# diagrama_robot.net
KiCad netlist of a schematic drawn in EAGLE
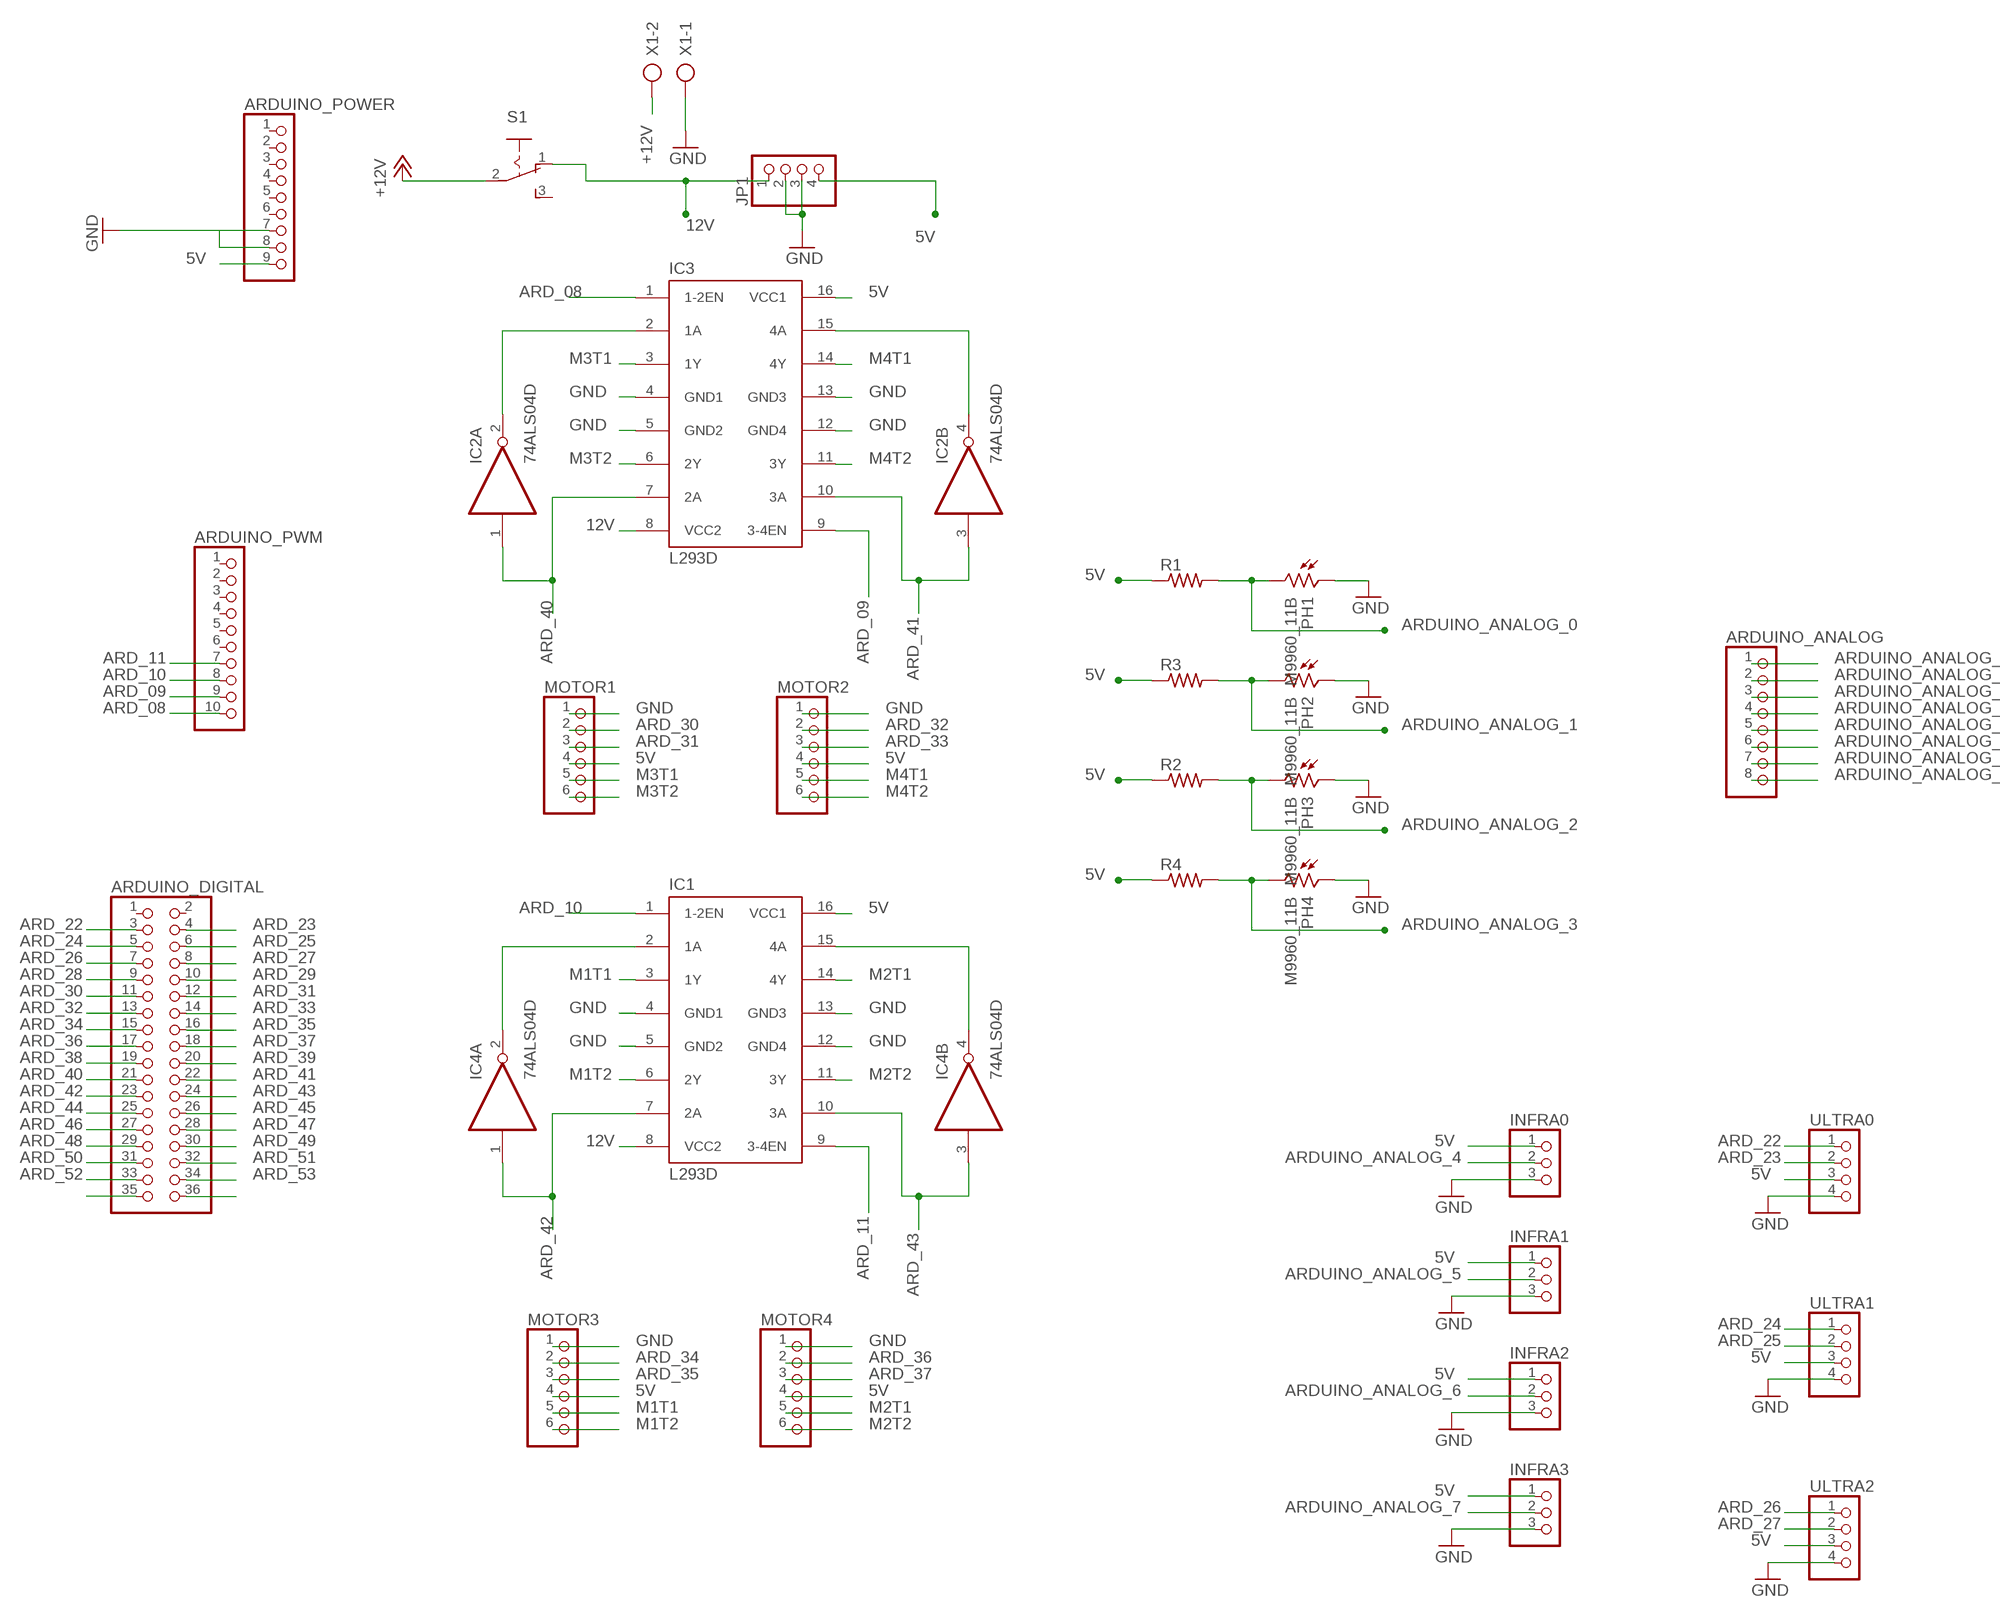
[diagram p0: schematic, sheet 1]

(export (version "E")
  (design (tool "Eeschema 10.0.6"))
  (components
    (comp (ref "ARDUINO_ANALOG")
      (value "PINHD-1X8")
      (footprint "eagle-import:1X08")
      (libsource (lib "eagle-import") (part "PINHD-1X8"))
    )
    (comp (ref "ARDUINO_DIGITAL")
      (value "PINHD-2X18")
      (footprint "eagle-import:2X18")
      (libsource (lib "eagle-import") (part "PINHD-2X18"))
    )
    (comp (ref "ARDUINO_POWER")
      (value "PINHD-1X9")
      (footprint "eagle-import:1X09")
      (libsource (lib "eagle-import") (part "PINHD-1X9"))
    )
    (comp (ref "ARDUINO_PWM")
      (value "PINHD-1X10")
      (footprint "eagle-import:1X10")
      (libsource (lib "eagle-import") (part "PINHD-1X10"))
    )
    (comp (ref "IC1")
      (value "L293D")
      (footprint "eagle-import:DIL16")
      (libsource (lib "eagle-import") (part "L293D"))
    )
    (comp (ref "IC2")
      (value "74ALS04D")
      (footprint "eagle-import:SO14")
      (libsource (lib "eagle-import") (part "7404DALS"))
    )
    (comp (ref "IC3")
      (value "L293D")
      (footprint "eagle-import:DIL16")
      (libsource (lib "eagle-import") (part "L293D"))
    )
    (comp (ref "IC4")
      (value "74ALS04D")
      (footprint "eagle-import:SO14")
      (libsource (lib "eagle-import") (part "7404DALS"))
    )
    (comp (ref "INFRA0")
      (value "PINHD-1X3")
      (footprint "eagle-import:1X03")
      (libsource (lib "eagle-import") (part "PINHD-1X3"))
    )
    (comp (ref "INFRA1")
      (value "PINHD-1X3")
      (footprint "eagle-import:1X03")
      (libsource (lib "eagle-import") (part "PINHD-1X3"))
    )
    (comp (ref "INFRA2")
      (value "PINHD-1X3")
      (footprint "eagle-import:1X03")
      (libsource (lib "eagle-import") (part "PINHD-1X3"))
    )
    (comp (ref "INFRA3")
      (value "PINHD-1X3")
      (footprint "eagle-import:1X03")
      (libsource (lib "eagle-import") (part "PINHD-1X3"))
    )
    (comp (ref "JP1")
      (value "PINHD-1X4")
      (footprint "eagle-import:1X04")
      (libsource (lib "eagle-import") (part "PINHD-1X4"))
    )
    (comp (ref "MOTOR1")
      (value "PINHD-1X6")
      (footprint "eagle-import:1X06")
      (libsource (lib "eagle-import") (part "PINHD-1X6"))
    )
    (comp (ref "MOTOR2")
      (value "PINHD-1X6")
      (footprint "eagle-import:1X06")
      (libsource (lib "eagle-import") (part "PINHD-1X6"))
    )
    (comp (ref "MOTOR3")
      (value "PINHD-1X6")
      (footprint "eagle-import:1X06")
      (libsource (lib "eagle-import") (part "PINHD-1X6"))
    )
    (comp (ref "MOTOR4")
      (value "PINHD-1X6")
      (footprint "eagle-import:1X06")
      (libsource (lib "eagle-import") (part "PINHD-1X6"))
    )
    (comp (ref "PH1")
      (value "M9960_11B")
      (footprint "eagle-import:M9960")
      (libsource (lib "eagle-import") (part "M9960_11B"))
    )
    (comp (ref "PH2")
      (value "M9960_11B")
      (footprint "eagle-import:M9960")
      (libsource (lib "eagle-import") (part "M9960_11B"))
    )
    (comp (ref "PH3")
      (value "M9960_11B")
      (footprint "eagle-import:M9960")
      (libsource (lib "eagle-import") (part "M9960_11B"))
    )
    (comp (ref "PH4")
      (value "M9960_11B")
      (footprint "eagle-import:M9960")
      (libsource (lib "eagle-import") (part "M9960_11B"))
    )
    (comp (ref "R1")
      (value "R-US_0204/2V")
      (footprint "eagle-import:0204V")
      (libsource (lib "eagle-import") (part "R-US_0204/2V"))
    )
    (comp (ref "R2")
      (value "R-US_0204/2V")
      (footprint "eagle-import:0204V")
      (libsource (lib "eagle-import") (part "R-US_0204/2V"))
    )
    (comp (ref "R3")
      (value "R-US_0204/2V")
      (footprint "eagle-import:0204V")
      (libsource (lib "eagle-import") (part "R-US_0204/2V"))
    )
    (comp (ref "R4")
      (value "R-US_0204/2V")
      (footprint "eagle-import:0204V")
      (libsource (lib "eagle-import") (part "R-US_0204/2V"))
    )
    (comp (ref "S1")
      (value "255SB")
      (footprint "eagle-import:255SB")
      (libsource (lib "eagle-import") (part "255SB"))
    )
    (comp (ref "ULTRA0")
      (value "PINHD-1X4")
      (footprint "eagle-import:1X04")
      (libsource (lib "eagle-import") (part "PINHD-1X4"))
    )
    (comp (ref "ULTRA1")
      (value "PINHD-1X4")
      (footprint "eagle-import:1X04")
      (libsource (lib "eagle-import") (part "PINHD-1X4"))
    )
    (comp (ref "ULTRA2")
      (value "PINHD-1X4")
      (footprint "eagle-import:1X04")
      (libsource (lib "eagle-import") (part "PINHD-1X4"))
    )
    (comp (ref "X1")
      (value "AK500/2-H")
      (footprint "eagle-import:AK500_2-H")
      (libsource (lib "eagle-import") (part "AK500/2-H"))
    )
  )
  (nets
    (net (code "1") (name "+12V") (class "Default")
      (node (ref "S1") (pin "2") (pinfunction "P_2") (pintype "passive"))
      (node (ref "X1") (pin "2") (pinfunction "KL_2") (pintype "passive"))
    )
    (net (code "2") (name "/5V") (class "Default")
      (node (ref "ARDUINO_POWER") (pin "9") (pinfunction "9_9") (pintype "passive"))
      (node (ref "IC1") (pin "16") (pinfunction "VCC1_16") (pintype "power_in"))
      (node (ref "IC3") (pin "16") (pinfunction "VCC1_16") (pintype "power_in"))
      (node (ref "INFRA0") (pin "1") (pinfunction "1_1") (pintype "passive"))
      (node (ref "INFRA1") (pin "1") (pinfunction "1_1") (pintype "passive"))
      (node (ref "INFRA2") (pin "1") (pinfunction "1_1") (pintype "passive"))
      (node (ref "INFRA3") (pin "1") (pinfunction "1_1") (pintype "passive"))
      (node (ref "JP1") (pin "4") (pinfunction "4_4") (pintype "passive"))
      (node (ref "MOTOR1") (pin "4") (pinfunction "4_4") (pintype "passive"))
      (node (ref "MOTOR2") (pin "4") (pinfunction "4_4") (pintype "passive"))
      (node (ref "MOTOR3") (pin "4") (pinfunction "4_4") (pintype "passive"))
      (node (ref "MOTOR4") (pin "4") (pinfunction "4_4") (pintype "passive"))
      (node (ref "R1") (pin "1") (pinfunction "1_1") (pintype "passive"))
      (node (ref "R2") (pin "1") (pinfunction "1_1") (pintype "passive"))
      (node (ref "R3") (pin "1") (pinfunction "1_1") (pintype "passive"))
      (node (ref "R4") (pin "1") (pinfunction "1_1") (pintype "passive"))
      (node (ref "ULTRA0") (pin "3") (pinfunction "3_3") (pintype "passive"))
      (node (ref "ULTRA1") (pin "3") (pinfunction "3_3") (pintype "passive"))
      (node (ref "ULTRA2") (pin "3") (pinfunction "3_3") (pintype "passive"))
    )
    (net (code "3") (name "/12V") (class "Default")
      (node (ref "IC1") (pin "8") (pinfunction "VCC2_8") (pintype "power_in"))
      (node (ref "IC3") (pin "8") (pinfunction "VCC2_8") (pintype "power_in"))
      (node (ref "JP1") (pin "1") (pinfunction "1_1") (pintype "passive"))
      (node (ref "S1") (pin "1") (pinfunction "O_1") (pintype "passive"))
    )
    (net (code "4") (name "/ARDUINO_ANALOG_0") (class "Default")
      (node (ref "ARDUINO_ANALOG") (pin "1") (pinfunction "1_1") (pintype "passive"))
      (node (ref "PH1") (pin "2") (pinfunction "2_2") (pintype "passive"))
      (node (ref "R1") (pin "2") (pinfunction "2_2") (pintype "passive"))
    )
    (net (code "5") (name "/ARDUINO_ANALOG_1") (class "Default")
      (node (ref "ARDUINO_ANALOG") (pin "2") (pinfunction "2_2") (pintype "passive"))
      (node (ref "PH2") (pin "2") (pinfunction "2_2") (pintype "passive"))
      (node (ref "R3") (pin "2") (pinfunction "2_2") (pintype "passive"))
    )
    (net (code "6") (name "/ARDUINO_ANALOG_2") (class "Default")
      (node (ref "ARDUINO_ANALOG") (pin "3") (pinfunction "3_3") (pintype "passive"))
      (node (ref "PH3") (pin "2") (pinfunction "2_2") (pintype "passive"))
      (node (ref "R2") (pin "2") (pinfunction "2_2") (pintype "passive"))
    )
    (net (code "7") (name "/ARDUINO_ANALOG_3") (class "Default")
      (node (ref "ARDUINO_ANALOG") (pin "4") (pinfunction "4_4") (pintype "passive"))
      (node (ref "PH4") (pin "2") (pinfunction "2_2") (pintype "passive"))
      (node (ref "R4") (pin "2") (pinfunction "2_2") (pintype "passive"))
    )
    (net (code "8") (name "/ARDUINO_ANALOG_4") (class "Default")
      (node (ref "ARDUINO_ANALOG") (pin "5") (pinfunction "5_5") (pintype "passive"))
      (node (ref "INFRA0") (pin "2") (pinfunction "2_2") (pintype "passive"))
    )
    (net (code "9") (name "/ARDUINO_ANALOG_5") (class "Default")
      (node (ref "ARDUINO_ANALOG") (pin "6") (pinfunction "6_6") (pintype "passive"))
      (node (ref "INFRA1") (pin "2") (pinfunction "2_2") (pintype "passive"))
    )
    (net (code "10") (name "/ARDUINO_ANALOG_6") (class "Default")
      (node (ref "ARDUINO_ANALOG") (pin "7") (pinfunction "7_7") (pintype "passive"))
      (node (ref "INFRA2") (pin "2") (pinfunction "2_2") (pintype "passive"))
    )
    (net (code "11") (name "/ARDUINO_ANALOG_7") (class "Default")
      (node (ref "ARDUINO_ANALOG") (pin "8") (pinfunction "8_8") (pintype "passive"))
      (node (ref "INFRA3") (pin "2") (pinfunction "2_2") (pintype "passive"))
    )
    (net (code "12") (name "/ARD_08") (class "Default")
      (node (ref "ARDUINO_PWM") (pin "10") (pinfunction "10_10") (pintype "passive"))
      (node (ref "IC3") (pin "1") (pinfunction "1-2EN_1") (pintype "input"))
    )
    (net (code "13") (name "/ARD_09") (class "Default")
      (node (ref "ARDUINO_PWM") (pin "9") (pinfunction "9_9") (pintype "passive"))
      (node (ref "IC3") (pin "9") (pinfunction "3-4EN_9") (pintype "input"))
    )
    (net (code "14") (name "/ARD_10") (class "Default")
      (node (ref "ARDUINO_PWM") (pin "8") (pinfunction "8_8") (pintype "passive"))
      (node (ref "IC1") (pin "1") (pinfunction "1-2EN_1") (pintype "input"))
    )
    (net (code "15") (name "/ARD_11") (class "Default")
      (node (ref "ARDUINO_PWM") (pin "7") (pinfunction "7_7") (pintype "passive"))
      (node (ref "IC1") (pin "9") (pinfunction "3-4EN_9") (pintype "input"))
    )
    (net (code "16") (name "/ARD_22") (class "Default")
      (node (ref "ARDUINO_DIGITAL") (pin "3") (pinfunction "3_3") (pintype "passive"))
      (node (ref "ULTRA0") (pin "1") (pinfunction "1_1") (pintype "passive"))
    )
    (net (code "17") (name "/ARD_23") (class "Default")
      (node (ref "ARDUINO_DIGITAL") (pin "4") (pinfunction "4_4") (pintype "passive"))
      (node (ref "ULTRA0") (pin "2") (pinfunction "2_2") (pintype "passive"))
    )
    (net (code "18") (name "/ARD_24") (class "Default")
      (node (ref "ARDUINO_DIGITAL") (pin "5") (pinfunction "5_5") (pintype "passive"))
      (node (ref "ULTRA1") (pin "1") (pinfunction "1_1") (pintype "passive"))
    )
    (net (code "19") (name "/ARD_25") (class "Default")
      (node (ref "ARDUINO_DIGITAL") (pin "6") (pinfunction "6_6") (pintype "passive"))
      (node (ref "ULTRA1") (pin "2") (pinfunction "2_2") (pintype "passive"))
    )
    (net (code "20") (name "/ARD_26") (class "Default")
      (node (ref "ARDUINO_DIGITAL") (pin "7") (pinfunction "7_7") (pintype "passive"))
      (node (ref "ULTRA2") (pin "1") (pinfunction "1_1") (pintype "passive"))
    )
    (net (code "21") (name "/ARD_27") (class "Default")
      (node (ref "ARDUINO_DIGITAL") (pin "8") (pinfunction "8_8") (pintype "passive"))
      (node (ref "ULTRA2") (pin "2") (pinfunction "2_2") (pintype "passive"))
    )
    (net (code "22") (name "/ARD_28") (class "Default")
      (node (ref "ARDUINO_DIGITAL") (pin "9") (pinfunction "9_9") (pintype "passive"))
    )
    (net (code "23") (name "/ARD_29") (class "Default")
      (node (ref "ARDUINO_DIGITAL") (pin "10") (pinfunction "10_10") (pintype "passive"))
    )
    (net (code "24") (name "/ARD_30") (class "Default")
      (node (ref "ARDUINO_DIGITAL") (pin "11") (pinfunction "11_11") (pintype "passive"))
      (node (ref "MOTOR1") (pin "2") (pinfunction "2_2") (pintype "passive"))
    )
    (net (code "25") (name "/ARD_31") (class "Default")
      (node (ref "ARDUINO_DIGITAL") (pin "12") (pinfunction "12_12") (pintype "passive"))
      (node (ref "MOTOR1") (pin "3") (pinfunction "3_3") (pintype "passive"))
    )
    (net (code "26") (name "/ARD_32") (class "Default")
      (node (ref "ARDUINO_DIGITAL") (pin "13") (pinfunction "13_13") (pintype "passive"))
      (node (ref "MOTOR2") (pin "2") (pinfunction "2_2") (pintype "passive"))
    )
    (net (code "27") (name "/ARD_33") (class "Default")
      (node (ref "ARDUINO_DIGITAL") (pin "14") (pinfunction "14_14") (pintype "passive"))
      (node (ref "MOTOR2") (pin "3") (pinfunction "3_3") (pintype "passive"))
    )
    (net (code "28") (name "/ARD_34") (class "Default")
      (node (ref "ARDUINO_DIGITAL") (pin "15") (pinfunction "15_15") (pintype "passive"))
      (node (ref "MOTOR3") (pin "2") (pinfunction "2_2") (pintype "passive"))
    )
    (net (code "29") (name "/ARD_35") (class "Default")
      (node (ref "ARDUINO_DIGITAL") (pin "16") (pinfunction "16_16") (pintype "passive"))
      (node (ref "MOTOR3") (pin "3") (pinfunction "3_3") (pintype "passive"))
    )
    (net (code "30") (name "/ARD_36") (class "Default")
      (node (ref "ARDUINO_DIGITAL") (pin "17") (pinfunction "17_17") (pintype "passive"))
      (node (ref "MOTOR4") (pin "2") (pinfunction "2_2") (pintype "passive"))
    )
    (net (code "31") (name "/ARD_37") (class "Default")
      (node (ref "ARDUINO_DIGITAL") (pin "18") (pinfunction "18_18") (pintype "passive"))
      (node (ref "MOTOR4") (pin "3") (pinfunction "3_3") (pintype "passive"))
    )
    (net (code "32") (name "/ARD_38") (class "Default")
      (node (ref "ARDUINO_DIGITAL") (pin "19") (pinfunction "19_19") (pintype "passive"))
    )
    (net (code "33") (name "/ARD_39") (class "Default")
      (node (ref "ARDUINO_DIGITAL") (pin "20") (pinfunction "20_20") (pintype "passive"))
    )
    (net (code "34") (name "/ARD_40") (class "Default")
      (node (ref "ARDUINO_DIGITAL") (pin "21") (pinfunction "21_21") (pintype "passive"))
      (node (ref "IC2") (pin "1") (pinfunction "I_1") (pintype "input"))
      (node (ref "IC3") (pin "7") (pinfunction "2A_7") (pintype "input"))
    )
    (net (code "35") (name "/ARD_41") (class "Default")
      (node (ref "ARDUINO_DIGITAL") (pin "22") (pinfunction "22_22") (pintype "passive"))
      (node (ref "IC2") (pin "3") (pinfunction "I_3") (pintype "input"))
      (node (ref "IC3") (pin "10") (pinfunction "3A_10") (pintype "input"))
    )
    (net (code "36") (name "/ARD_42") (class "Default")
      (node (ref "ARDUINO_DIGITAL") (pin "23") (pinfunction "23_23") (pintype "passive"))
      (node (ref "IC1") (pin "7") (pinfunction "2A_7") (pintype "input"))
      (node (ref "IC4") (pin "1") (pinfunction "I_1") (pintype "input"))
    )
    (net (code "37") (name "/ARD_43") (class "Default")
      (node (ref "ARDUINO_DIGITAL") (pin "24") (pinfunction "24_24") (pintype "passive"))
      (node (ref "IC1") (pin "10") (pinfunction "3A_10") (pintype "input"))
      (node (ref "IC4") (pin "3") (pinfunction "I_3") (pintype "input"))
    )
    (net (code "38") (name "/ARD_44") (class "Default")
      (node (ref "ARDUINO_DIGITAL") (pin "25") (pinfunction "25_25") (pintype "passive"))
    )
    (net (code "39") (name "/ARD_45") (class "Default")
      (node (ref "ARDUINO_DIGITAL") (pin "26") (pinfunction "26_26") (pintype "passive"))
    )
    (net (code "40") (name "/ARD_46") (class "Default")
      (node (ref "ARDUINO_DIGITAL") (pin "27") (pinfunction "27_27") (pintype "passive"))
    )
    (net (code "41") (name "/ARD_47") (class "Default")
      (node (ref "ARDUINO_DIGITAL") (pin "28") (pinfunction "28_28") (pintype "passive"))
    )
    (net (code "42") (name "/ARD_48") (class "Default")
      (node (ref "ARDUINO_DIGITAL") (pin "29") (pinfunction "29_29") (pintype "passive"))
    )
    (net (code "43") (name "/ARD_49") (class "Default")
      (node (ref "ARDUINO_DIGITAL") (pin "30") (pinfunction "30_30") (pintype "passive"))
    )
    (net (code "44") (name "/ARD_50") (class "Default")
      (node (ref "ARDUINO_DIGITAL") (pin "31") (pinfunction "31_31") (pintype "passive"))
    )
    (net (code "45") (name "/ARD_51") (class "Default")
      (node (ref "ARDUINO_DIGITAL") (pin "32") (pinfunction "32_32") (pintype "passive"))
    )
    (net (code "46") (name "/ARD_52") (class "Default")
      (node (ref "ARDUINO_DIGITAL") (pin "33") (pinfunction "33_33") (pintype "passive"))
    )
    (net (code "47") (name "/ARD_53") (class "Default")
      (node (ref "ARDUINO_DIGITAL") (pin "34") (pinfunction "34_34") (pintype "passive"))
    )
    (net (code "48") (name "/M1T1") (class "Default")
      (node (ref "IC1") (pin "3") (pinfunction "1Y_3") (pintype "output"))
      (node (ref "MOTOR3") (pin "5") (pinfunction "5_5") (pintype "passive"))
    )
    (net (code "49") (name "/M1T2") (class "Default")
      (node (ref "IC1") (pin "6") (pinfunction "2Y_6") (pintype "output"))
      (node (ref "MOTOR3") (pin "6") (pinfunction "6_6") (pintype "passive"))
    )
    (net (code "50") (name "/M2T1") (class "Default")
      (node (ref "IC1") (pin "14") (pinfunction "4Y_14") (pintype "output"))
      (node (ref "MOTOR4") (pin "5") (pinfunction "5_5") (pintype "passive"))
    )
    (net (code "51") (name "/M2T2") (class "Default")
      (node (ref "IC1") (pin "11") (pinfunction "3Y_11") (pintype "output"))
      (node (ref "MOTOR4") (pin "6") (pinfunction "6_6") (pintype "passive"))
    )
    (net (code "52") (name "/M3T1") (class "Default")
      (node (ref "IC3") (pin "3") (pinfunction "1Y_3") (pintype "output"))
      (node (ref "MOTOR1") (pin "5") (pinfunction "5_5") (pintype "passive"))
    )
    (net (code "53") (name "/M3T2") (class "Default")
      (node (ref "IC3") (pin "6") (pinfunction "2Y_6") (pintype "output"))
      (node (ref "MOTOR1") (pin "6") (pinfunction "6_6") (pintype "passive"))
    )
    (net (code "54") (name "/M4T1") (class "Default")
      (node (ref "IC3") (pin "14") (pinfunction "4Y_14") (pintype "output"))
      (node (ref "MOTOR2") (pin "5") (pinfunction "5_5") (pintype "passive"))
    )
    (net (code "55") (name "/M4T2") (class "Default")
      (node (ref "IC3") (pin "11") (pinfunction "3Y_11") (pintype "output"))
      (node (ref "MOTOR2") (pin "6") (pinfunction "6_6") (pintype "passive"))
    )
    (net (code "56") (name "GND") (class "Default")
      (node (ref "ARDUINO_POWER") (pin "7") (pinfunction "7_7") (pintype "passive"))
      (node (ref "ARDUINO_POWER") (pin "8") (pinfunction "8_8") (pintype "passive"))
      (node (ref "IC1") (pin "12") (pinfunction "GND4_12") (pintype "power_in"))
      (node (ref "IC1") (pin "13") (pinfunction "GND3_13") (pintype "power_in"))
      (node (ref "IC1") (pin "4") (pinfunction "GND1_4") (pintype "power_in"))
      (node (ref "IC1") (pin "5") (pinfunction "GND2_5") (pintype "power_in"))
      (node (ref "IC3") (pin "12") (pinfunction "GND4_12") (pintype "power_in"))
      (node (ref "IC3") (pin "13") (pinfunction "GND3_13") (pintype "power_in"))
      (node (ref "IC3") (pin "4") (pinfunction "GND1_4") (pintype "power_in"))
      (node (ref "IC3") (pin "5") (pinfunction "GND2_5") (pintype "power_in"))
      (node (ref "INFRA0") (pin "3") (pinfunction "3_3") (pintype "passive"))
      (node (ref "INFRA1") (pin "3") (pinfunction "3_3") (pintype "passive"))
      (node (ref "INFRA2") (pin "3") (pinfunction "3_3") (pintype "passive"))
      (node (ref "INFRA3") (pin "3") (pinfunction "3_3") (pintype "passive"))
      (node (ref "JP1") (pin "2") (pinfunction "2_2") (pintype "passive"))
      (node (ref "JP1") (pin "3") (pinfunction "3_3") (pintype "passive"))
      (node (ref "MOTOR1") (pin "1") (pinfunction "1_1") (pintype "passive"))
      (node (ref "MOTOR2") (pin "1") (pinfunction "1_1") (pintype "passive"))
      (node (ref "MOTOR3") (pin "1") (pinfunction "1_1") (pintype "passive"))
      (node (ref "MOTOR4") (pin "1") (pinfunction "1_1") (pintype "passive"))
      (node (ref "PH1") (pin "1") (pinfunction "1_1") (pintype "passive"))
      (node (ref "PH2") (pin "1") (pinfunction "1_1") (pintype "passive"))
      (node (ref "PH3") (pin "1") (pinfunction "1_1") (pintype "passive"))
      (node (ref "PH4") (pin "1") (pinfunction "1_1") (pintype "passive"))
      (node (ref "ULTRA0") (pin "4") (pinfunction "4_4") (pintype "passive"))
      (node (ref "ULTRA1") (pin "4") (pinfunction "4_4") (pintype "passive"))
      (node (ref "ULTRA2") (pin "4") (pinfunction "4_4") (pintype "passive"))
      (node (ref "X1") (pin "1") (pinfunction "KL_1") (pintype "passive"))
    )
    (net (code "57") (name "Net-(IC1-1A)") (class "Default")
      (node (ref "IC1") (pin "2") (pinfunction "1A_2") (pintype "input"))
      (node (ref "IC4") (pin "2") (pinfunction "O_2") (pintype "output"))
    )
    (net (code "58") (name "Net-(IC1-4A)") (class "Default")
      (node (ref "IC1") (pin "15") (pinfunction "4A_15") (pintype "input"))
      (node (ref "IC4") (pin "4") (pinfunction "O_4") (pintype "output"))
    )
    (net (code "59") (name "Net-(IC2A-O)") (class "Default")
      (node (ref "IC2") (pin "2") (pinfunction "O_2") (pintype "output"))
      (node (ref "IC3") (pin "2") (pinfunction "1A_2") (pintype "input"))
    )
    (net (code "60") (name "Net-(IC2B-O)") (class "Default")
      (node (ref "IC2") (pin "4") (pinfunction "O_4") (pintype "output"))
      (node (ref "IC3") (pin "15") (pinfunction "4A_15") (pintype "input"))
    )
    (net (code "61") (name "unconnected-(ARDUINO_DIGITAL-Pad1)") (class "Default")
      (node (ref "ARDUINO_DIGITAL") (pin "1") (pinfunction "1_1") (pintype "passive"))
    )
    (net (code "62") (name "unconnected-(ARDUINO_DIGITAL-Pad2)") (class "Default")
      (node (ref "ARDUINO_DIGITAL") (pin "2") (pinfunction "2_2") (pintype "passive"))
    )
    (net (code "63") (name "unconnected-(ARDUINO_DIGITAL-Pad35)") (class "Default")
      (node (ref "ARDUINO_DIGITAL") (pin "35") (pinfunction "35_35") (pintype "passive"))
    )
    (net (code "64") (name "unconnected-(ARDUINO_DIGITAL-Pad36)") (class "Default")
      (node (ref "ARDUINO_DIGITAL") (pin "36") (pinfunction "36_36") (pintype "passive"))
    )
    (net (code "65") (name "unconnected-(ARDUINO_POWER-Pad1)") (class "Default")
      (node (ref "ARDUINO_POWER") (pin "1") (pinfunction "1_1") (pintype "passive"))
    )
    (net (code "66") (name "unconnected-(ARDUINO_POWER-Pad2)") (class "Default")
      (node (ref "ARDUINO_POWER") (pin "2") (pinfunction "2_2") (pintype "passive"))
    )
    (net (code "67") (name "unconnected-(ARDUINO_POWER-Pad3)") (class "Default")
      (node (ref "ARDUINO_POWER") (pin "3") (pinfunction "3_3") (pintype "passive"))
    )
    (net (code "68") (name "unconnected-(ARDUINO_POWER-Pad4)") (class "Default")
      (node (ref "ARDUINO_POWER") (pin "4") (pinfunction "4_4") (pintype "passive"))
    )
    (net (code "69") (name "unconnected-(ARDUINO_POWER-Pad5)") (class "Default")
      (node (ref "ARDUINO_POWER") (pin "5") (pinfunction "5_5") (pintype "passive"))
    )
    (net (code "70") (name "unconnected-(ARDUINO_POWER-Pad6)") (class "Default")
      (node (ref "ARDUINO_POWER") (pin "6") (pinfunction "6_6") (pintype "passive"))
    )
    (net (code "71") (name "unconnected-(ARDUINO_PWM-Pad1)") (class "Default")
      (node (ref "ARDUINO_PWM") (pin "1") (pinfunction "1_1") (pintype "passive"))
    )
    (net (code "72") (name "unconnected-(ARDUINO_PWM-Pad2)") (class "Default")
      (node (ref "ARDUINO_PWM") (pin "2") (pinfunction "2_2") (pintype "passive"))
    )
    (net (code "73") (name "unconnected-(ARDUINO_PWM-Pad3)") (class "Default")
      (node (ref "ARDUINO_PWM") (pin "3") (pinfunction "3_3") (pintype "passive"))
    )
    (net (code "74") (name "unconnected-(ARDUINO_PWM-Pad4)") (class "Default")
      (node (ref "ARDUINO_PWM") (pin "4") (pinfunction "4_4") (pintype "passive"))
    )
    (net (code "75") (name "unconnected-(ARDUINO_PWM-Pad5)") (class "Default")
      (node (ref "ARDUINO_PWM") (pin "5") (pinfunction "5_5") (pintype "passive"))
    )
    (net (code "76") (name "unconnected-(ARDUINO_PWM-Pad6)") (class "Default")
      (node (ref "ARDUINO_PWM") (pin "6") (pinfunction "6_6") (pintype "passive"))
    )
    (net (code "77") (name "unconnected-(S1-S-Pad3)") (class "Default")
      (node (ref "S1") (pin "3") (pinfunction "S_3") (pintype "passive"))
    )
  )
)
